# ili9341-SpiLcd.net
KiCad netlist of a schematic drawn in Altium Designer
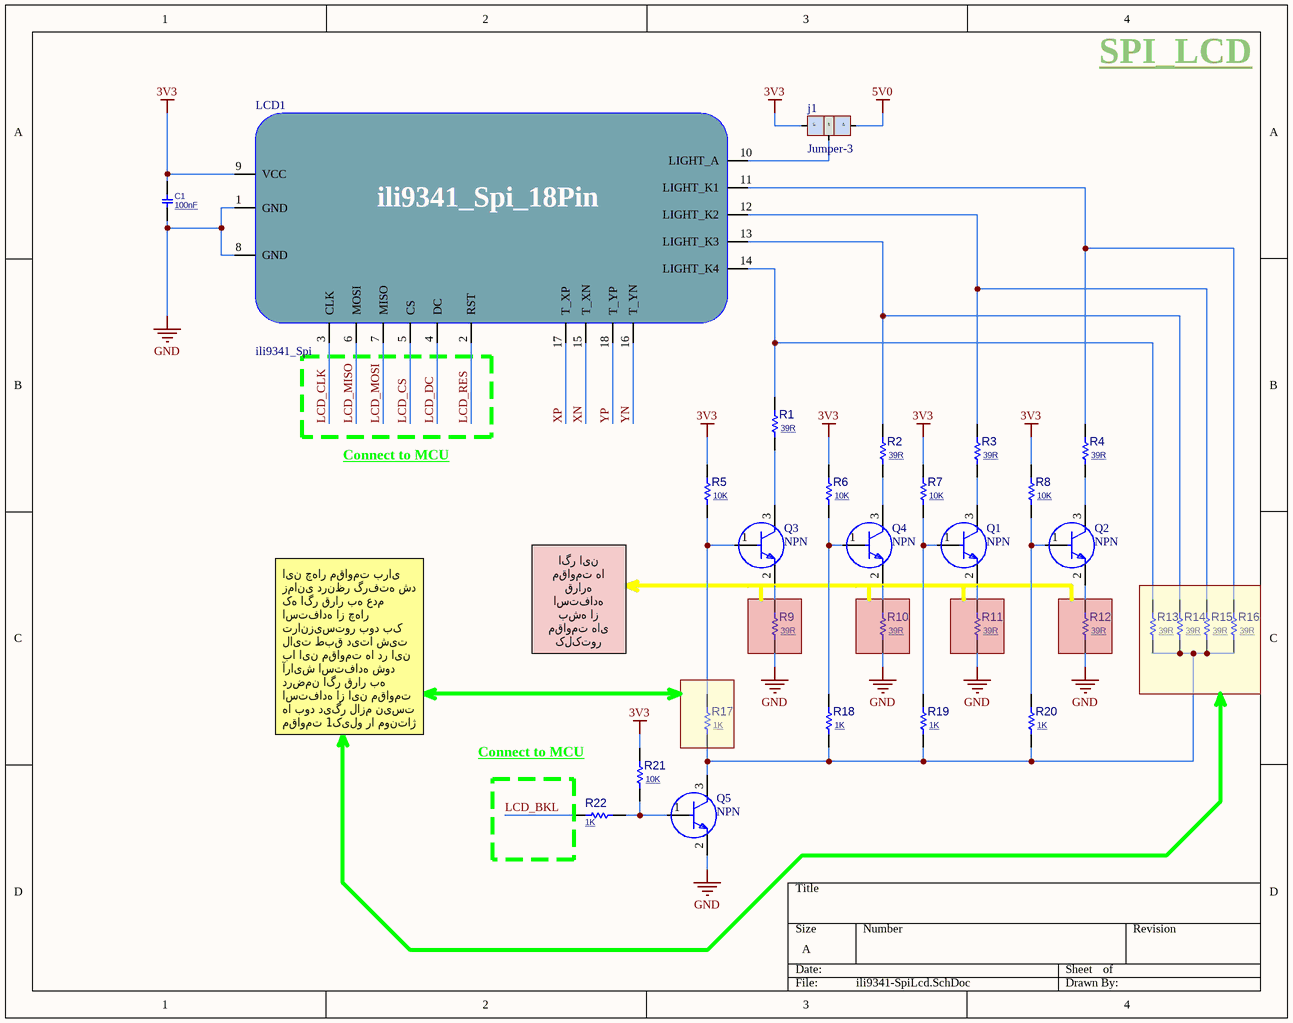
[diagram p0: ili9341-SpiLcd.SchDoc]

(export (version "E")
  (design (tool "Eeschema 10.0.6"))
  (components
    (comp (ref "C1")
      (value "100nF")
      (footprint "C0603")
      (description "CAP, MLCC, -F, -V, MATERIAL, -%, 0201")
      (fields (field (name "MANF_P#") "MANF_PART#"))
      (libsource (lib "passive_smd") (part "CAP_SMD_MLCC_0603"))
    )
    (comp (ref "j1") (value "Jumper-3") (footprint "jumper-3") (libsource (lib "jumper") (part "Jumper-3")))
    (comp (ref "LCD1")
      (value "ili9341_Spi")
      (footprint "ILI9341_Spi_18Pin_2")
      (libsource (lib "ili9341_1pin_Spi") (part "ili9341_Spi"))
    )
    (comp (ref "Q1")
      (value "NPN")
      (footprint "FP-SOT23-IPC_A")
      (libsource (lib "NPN-SOT-23") (part "CMP-2000-04931-2"))
    )
    (comp (ref "Q2")
      (value "NPN")
      (footprint "FP-SOT23-IPC_A")
      (libsource (lib "NPN-SOT-23") (part "CMP-2000-04931-2"))
    )
    (comp (ref "Q3")
      (value "NPN")
      (footprint "FP-SOT23-IPC_A")
      (libsource (lib "NPN-SOT-23") (part "CMP-2000-04931-2"))
    )
    (comp (ref "Q4")
      (value "NPN")
      (footprint "FP-SOT23-IPC_A")
      (libsource (lib "NPN-SOT-23") (part "CMP-2000-04931-2"))
    )
    (comp (ref "Q5")
      (value "NPN")
      (footprint "FP-SOT23-IPC_A")
      (libsource (lib "NPN-SOT-23") (part "CMP-2000-04931-2"))
    )
    (comp (ref "R1")
      (value "39R")
      (footprint "R0603")
      (description "RESISTOR, SMD")
      (libsource (lib "passive_smd") (part "RES_SMD"))
    )
    (comp (ref "R2")
      (value "39R")
      (footprint "R0603")
      (description "RESISTOR, SMD")
      (libsource (lib "passive_smd") (part "RES_SMD"))
    )
    (comp (ref "R3")
      (value "39R")
      (footprint "R0603")
      (description "RESISTOR, SMD")
      (libsource (lib "passive_smd") (part "RES_SMD"))
    )
    (comp (ref "R4")
      (value "39R")
      (footprint "R0603")
      (description "RESISTOR, SMD")
      (libsource (lib "passive_smd") (part "RES_SMD"))
    )
    (comp (ref "R5")
      (value "10K")
      (footprint "R0603")
      (description "RESISTOR, SMD")
      (libsource (lib "passive_smd") (part "RES_SMD"))
    )
    (comp (ref "R6")
      (value "10K")
      (footprint "R0603")
      (description "RESISTOR, SMD")
      (libsource (lib "passive_smd") (part "RES_SMD"))
    )
    (comp (ref "R7")
      (value "10K")
      (footprint "R0603")
      (description "RESISTOR, SMD")
      (libsource (lib "passive_smd") (part "RES_SMD"))
    )
    (comp (ref "R8")
      (value "10K")
      (footprint "R0603")
      (description "RESISTOR, SMD")
      (libsource (lib "passive_smd") (part "RES_SMD"))
    )
    (comp (ref "R9")
      (value "39R")
      (footprint "R0603")
      (description "RESISTOR, SMD")
      (libsource (lib "passive_smd") (part "RES_SMD"))
    )
    (comp (ref "R10")
      (value "39R")
      (footprint "R0603")
      (description "RESISTOR, SMD")
      (libsource (lib "passive_smd") (part "RES_SMD"))
    )
    (comp (ref "R11")
      (value "39R")
      (footprint "R0603")
      (description "RESISTOR, SMD")
      (libsource (lib "passive_smd") (part "RES_SMD"))
    )
    (comp (ref "R12")
      (value "39R")
      (footprint "R0603")
      (description "RESISTOR, SMD")
      (libsource (lib "passive_smd") (part "RES_SMD"))
    )
    (comp (ref "R13")
      (value "39R")
      (footprint "R0603")
      (description "RESISTOR, SMD")
      (libsource (lib "passive_smd") (part "RES_SMD"))
    )
    (comp (ref "R14")
      (value "39R")
      (footprint "R0603")
      (description "RESISTOR, SMD")
      (libsource (lib "passive_smd") (part "RES_SMD"))
    )
    (comp (ref "R15")
      (value "39R")
      (footprint "R0603")
      (description "RESISTOR, SMD")
      (libsource (lib "passive_smd") (part "RES_SMD"))
    )
    (comp (ref "R16")
      (value "39R")
      (footprint "R0603")
      (description "RESISTOR, SMD")
      (libsource (lib "passive_smd") (part "RES_SMD"))
    )
    (comp (ref "R17")
      (value "1K")
      (footprint "R0603")
      (description "RESISTOR, SMD")
      (libsource (lib "passive_smd") (part "RES_SMD"))
    )
    (comp (ref "R18")
      (value "1K")
      (footprint "R0603")
      (description "RESISTOR, SMD")
      (libsource (lib "passive_smd") (part "RES_SMD"))
    )
    (comp (ref "R19")
      (value "1K")
      (footprint "R0603")
      (description "RESISTOR, SMD")
      (libsource (lib "passive_smd") (part "RES_SMD"))
    )
    (comp (ref "R20")
      (value "1K")
      (footprint "R0603")
      (description "RESISTOR, SMD")
      (libsource (lib "passive_smd") (part "RES_SMD"))
    )
    (comp (ref "R21")
      (value "10K")
      (footprint "R0603")
      (description "RESISTOR, SMD")
      (libsource (lib "passive_smd") (part "RES_SMD"))
    )
    (comp (ref "R22")
      (value "1K")
      (footprint "R0603")
      (description "RESISTOR, SMD")
      (libsource (lib "passive_smd") (part "RES_SMD"))
    )
  )
  (nets
    (net (code "1") (name "/LCD_BKL") (class "Default")
      (node (ref "R22") (pin "2") (pinfunction "2_2") (pintype "passive"))
    )
    (net (code "2") (name "/LCD_CLK") (class "Default")
      (node (ref "LCD1") (pin "3") (pinfunction "CLK_3") (pintype "passive"))
    )
    (net (code "3") (name "/LCD_CS") (class "Default")
      (node (ref "LCD1") (pin "5") (pinfunction "CS_5") (pintype "passive"))
    )
    (net (code "4") (name "/LCD_DC") (class "Default")
      (node (ref "LCD1") (pin "4") (pinfunction "DC_4") (pintype "passive"))
    )
    (net (code "5") (name "/LCD_MISO") (class "Default")
      (node (ref "LCD1") (pin "6") (pinfunction "MOSI_6") (pintype "passive"))
    )
    (net (code "6") (name "/LCD_MOSI") (class "Default")
      (node (ref "LCD1") (pin "7") (pinfunction "MISO_7") (pintype "passive"))
    )
    (net (code "7") (name "/LCD_RES") (class "Default")
      (node (ref "LCD1") (pin "2") (pinfunction "RST_2") (pintype "passive"))
    )
    (net (code "8") (name "/XN") (class "Default")
      (node (ref "LCD1") (pin "15") (pinfunction "T_XN_15") (pintype "passive"))
    )
    (net (code "9") (name "/XP") (class "Default")
      (node (ref "LCD1") (pin "17") (pinfunction "T_XP_17") (pintype "passive"))
    )
    (net (code "10") (name "/YN") (class "Default")
      (node (ref "LCD1") (pin "16") (pinfunction "T_YN_16") (pintype "passive"))
    )
    (net (code "11") (name "/YP") (class "Default")
      (node (ref "LCD1") (pin "18") (pinfunction "T_YP_18") (pintype "passive"))
    )
    (net (code "12") (name "3V3") (class "Default")
      (node (ref "C1") (pin "2") (pinfunction "2_2") (pintype "passive"))
      (node (ref "LCD1") (pin "9") (pinfunction "VCC_9") (pintype "passive"))
      (node (ref "R21") (pin "2") (pinfunction "2_2") (pintype "passive"))
      (node (ref "R5") (pin "2") (pinfunction "2_2") (pintype "passive"))
      (node (ref "R6") (pin "2") (pinfunction "2_2") (pintype "passive"))
      (node (ref "R7") (pin "2") (pinfunction "2_2") (pintype "passive"))
      (node (ref "R8") (pin "2") (pinfunction "2_2") (pintype "passive"))
      (node (ref "j1") (pin "3") (pinfunction "3_3") (pintype "passive"))
    )
    (net (code "13") (name "5V0") (class "Default")
      (node (ref "j1") (pin "1") (pinfunction "1_1") (pintype "passive"))
    )
    (net (code "14") (name "GND") (class "Default")
      (node (ref "C1") (pin "1") (pinfunction "1_1") (pintype "passive"))
      (node (ref "LCD1") (pin "1") (pinfunction "GND_1") (pintype "passive"))
      (node (ref "LCD1") (pin "8") (pinfunction "GND_8") (pintype "passive"))
      (node (ref "Q5") (pin "2") (pinfunction "E_2") (pintype "passive"))
      (node (ref "R10") (pin "1") (pinfunction "1_1") (pintype "passive"))
      (node (ref "R11") (pin "1") (pinfunction "1_1") (pintype "passive"))
      (node (ref "R12") (pin "1") (pinfunction "1_1") (pintype "passive"))
      (node (ref "R9") (pin "1") (pinfunction "1_1") (pintype "passive"))
    )
    (net (code "15") (name "Net-(LCD1-LIGHT_A)") (class "Default")
      (node (ref "LCD1") (pin "10") (pinfunction "LIGHT_A_10") (pintype "passive"))
      (node (ref "j1") (pin "2") (pinfunction "2_2") (pintype "passive"))
    )
    (net (code "16") (name "Net-(LCD1-LIGHT_K1)") (class "Default")
      (node (ref "LCD1") (pin "11") (pinfunction "LIGHT_K1_11") (pintype "passive"))
      (node (ref "R16") (pin "2") (pinfunction "2_2") (pintype "passive"))
      (node (ref "R4") (pin "2") (pinfunction "2_2") (pintype "passive"))
    )
    (net (code "17") (name "Net-(LCD1-LIGHT_K2)") (class "Default")
      (node (ref "LCD1") (pin "12") (pinfunction "LIGHT_K2_12") (pintype "passive"))
      (node (ref "R15") (pin "2") (pinfunction "2_2") (pintype "passive"))
      (node (ref "R3") (pin "2") (pinfunction "2_2") (pintype "passive"))
    )
    (net (code "18") (name "Net-(LCD1-LIGHT_K3)") (class "Default")
      (node (ref "LCD1") (pin "13") (pinfunction "LIGHT_K3_13") (pintype "passive"))
      (node (ref "R14") (pin "2") (pinfunction "2_2") (pintype "passive"))
      (node (ref "R2") (pin "2") (pinfunction "2_2") (pintype "passive"))
    )
    (net (code "19") (name "Net-(LCD1-LIGHT_K4)") (class "Default")
      (node (ref "LCD1") (pin "14") (pinfunction "LIGHT_K4_14") (pintype "passive"))
      (node (ref "R1") (pin "2") (pinfunction "2_2") (pintype "passive"))
      (node (ref "R13") (pin "2") (pinfunction "2_2") (pintype "passive"))
    )
    (net (code "20") (name "Net-(Q1-B)") (class "Default")
      (node (ref "Q1") (pin "1") (pinfunction "B_1") (pintype "passive"))
      (node (ref "R19") (pin "2") (pinfunction "2_2") (pintype "passive"))
      (node (ref "R7") (pin "1") (pinfunction "1_1") (pintype "passive"))
    )
    (net (code "21") (name "Net-(Q1-C)") (class "Default")
      (node (ref "Q1") (pin "3") (pinfunction "C_3") (pintype "passive"))
      (node (ref "R3") (pin "1") (pinfunction "1_1") (pintype "passive"))
    )
    (net (code "22") (name "Net-(Q1-E)") (class "Default")
      (node (ref "Q1") (pin "2") (pinfunction "E_2") (pintype "passive"))
      (node (ref "R11") (pin "2") (pinfunction "2_2") (pintype "passive"))
    )
    (net (code "23") (name "Net-(Q2-B)") (class "Default")
      (node (ref "Q2") (pin "1") (pinfunction "B_1") (pintype "passive"))
      (node (ref "R20") (pin "2") (pinfunction "2_2") (pintype "passive"))
      (node (ref "R8") (pin "1") (pinfunction "1_1") (pintype "passive"))
    )
    (net (code "24") (name "Net-(Q2-C)") (class "Default")
      (node (ref "Q2") (pin "3") (pinfunction "C_3") (pintype "passive"))
      (node (ref "R4") (pin "1") (pinfunction "1_1") (pintype "passive"))
    )
    (net (code "25") (name "Net-(Q2-E)") (class "Default")
      (node (ref "Q2") (pin "2") (pinfunction "E_2") (pintype "passive"))
      (node (ref "R12") (pin "2") (pinfunction "2_2") (pintype "passive"))
    )
    (net (code "26") (name "Net-(Q3-B)") (class "Default")
      (node (ref "Q3") (pin "1") (pinfunction "B_1") (pintype "passive"))
      (node (ref "R17") (pin "2") (pinfunction "2_2") (pintype "passive"))
      (node (ref "R5") (pin "1") (pinfunction "1_1") (pintype "passive"))
    )
    (net (code "27") (name "Net-(Q3-C)") (class "Default")
      (node (ref "Q3") (pin "3") (pinfunction "C_3") (pintype "passive"))
      (node (ref "R1") (pin "1") (pinfunction "1_1") (pintype "passive"))
    )
    (net (code "28") (name "Net-(Q3-E)") (class "Default")
      (node (ref "Q3") (pin "2") (pinfunction "E_2") (pintype "passive"))
      (node (ref "R9") (pin "2") (pinfunction "2_2") (pintype "passive"))
    )
    (net (code "29") (name "Net-(Q4-B)") (class "Default")
      (node (ref "Q4") (pin "1") (pinfunction "B_1") (pintype "passive"))
      (node (ref "R18") (pin "2") (pinfunction "2_2") (pintype "passive"))
      (node (ref "R6") (pin "1") (pinfunction "1_1") (pintype "passive"))
    )
    (net (code "30") (name "Net-(Q4-C)") (class "Default")
      (node (ref "Q4") (pin "3") (pinfunction "C_3") (pintype "passive"))
      (node (ref "R2") (pin "1") (pinfunction "1_1") (pintype "passive"))
    )
    (net (code "31") (name "Net-(Q4-E)") (class "Default")
      (node (ref "Q4") (pin "2") (pinfunction "E_2") (pintype "passive"))
      (node (ref "R10") (pin "2") (pinfunction "2_2") (pintype "passive"))
    )
    (net (code "32") (name "Net-(Q5-B)") (class "Default")
      (node (ref "Q5") (pin "1") (pinfunction "B_1") (pintype "passive"))
      (node (ref "R21") (pin "1") (pinfunction "1_1") (pintype "passive"))
      (node (ref "R22") (pin "1") (pinfunction "1_1") (pintype "passive"))
    )
    (net (code "33") (name "Net-(Q5-C)") (class "Default")
      (node (ref "Q5") (pin "3") (pinfunction "C_3") (pintype "passive"))
      (node (ref "R13") (pin "1") (pinfunction "1_1") (pintype "passive"))
      (node (ref "R14") (pin "1") (pinfunction "1_1") (pintype "passive"))
      (node (ref "R15") (pin "1") (pinfunction "1_1") (pintype "passive"))
      (node (ref "R16") (pin "1") (pinfunction "1_1") (pintype "passive"))
      (node (ref "R17") (pin "1") (pinfunction "1_1") (pintype "passive"))
      (node (ref "R18") (pin "1") (pinfunction "1_1") (pintype "passive"))
      (node (ref "R19") (pin "1") (pinfunction "1_1") (pintype "passive"))
      (node (ref "R20") (pin "1") (pinfunction "1_1") (pintype "passive"))
    )
  )
)
